# SCH_simple-car_2026-01-17.net
KiCad netlist of a schematic drawn in EasyEDA
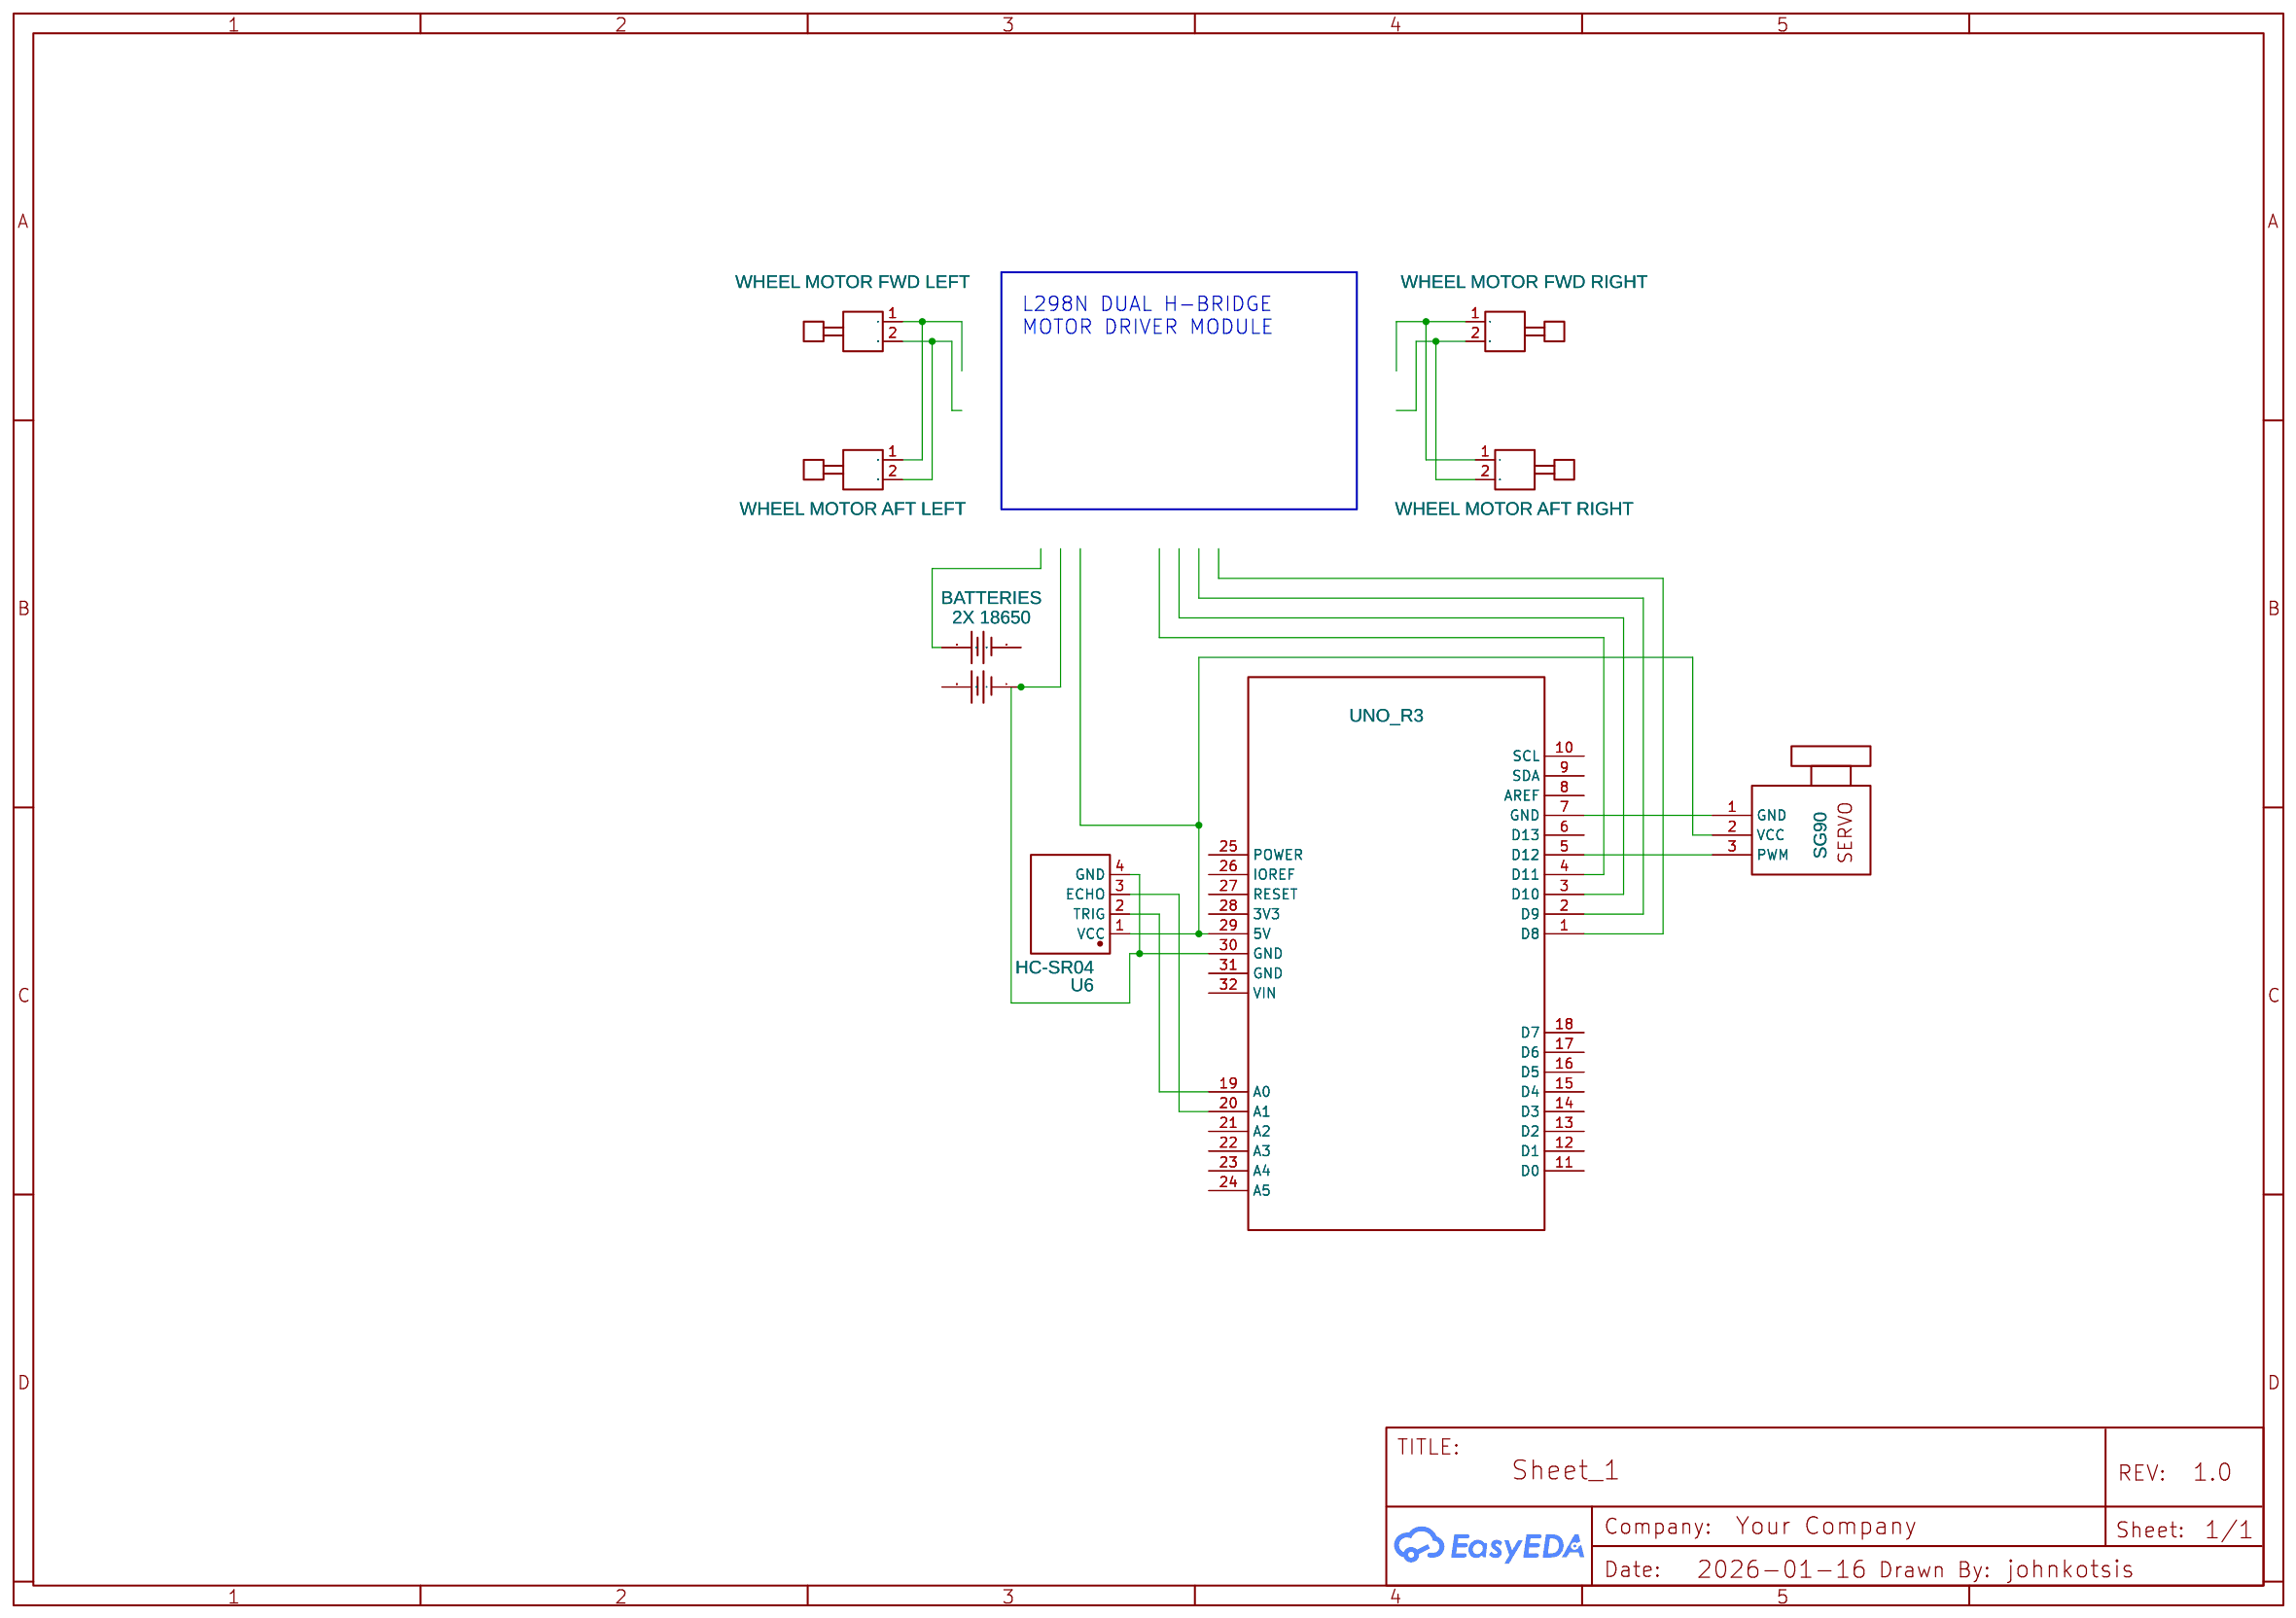
[diagram p0: schematic sheet]

(export (version "E")
  (design (tool "Eeschema 10.0.6"))
  (components
    (comp (ref "BATTERIES")
      (value "2X 18650")
      (fields
        (field (name "Manufacturer Part") "BH-18650-A1BJ034")
        (field (name "Manufacturer") "MYOUNG(美阳)")
      )
      (libsource (lib "") (part "BH-18650-A1BJ034"))
    )
    (comp (ref "P1") (value "UNO_R3") (libsource (lib "") (part "UNO_R3")))
    (comp (ref "U1")
      (value "SG90")
      (fields (field (name "Manufacturer Part") "ServoMotor"))
      (libsource (lib "") (part "SERVO MG995 COPY"))
    )
    (comp (ref "U2")
      (value "WHEEL MOTOR FWD LEFT")
      (fields (field (name "Manufacturer Part") "LCM04084521-B1") (field (name "Manufacturer") "LEADER(立得)"))
      (libsource (lib "") (part "LCM04084521-B1"))
    )
    (comp (ref "U3")
      (value "WHEEL MOTOR FWD RIGHT")
      (fields (field (name "Manufacturer Part") "LCM04084521-B1") (field (name "Manufacturer") "LEADER(立得)"))
      (libsource (lib "") (part "LCM04084521-B1_1"))
    )
    (comp (ref "U4")
      (value "WHEEL MOTOR AFT LEFT")
      (fields (field (name "Manufacturer Part") "LCM04084521-B1") (field (name "Manufacturer") "LEADER(立得)"))
      (libsource (lib "") (part "LCM04084521-B1"))
    )
    (comp (ref "U5")
      (value "WHEEL MOTOR AFT RIGHT")
      (fields (field (name "Manufacturer Part") "LCM04084521-B1") (field (name "Manufacturer") "LEADER(立得)"))
      (libsource (lib "") (part "LCM04084521-B1_1"))
    )
    (comp (ref "U6")
      (value "HC-SR04")
      (fields (field (name "Manufacturer") "Universal Microelectronics"))
      (libsource (lib "") (part "HC-SR04"))
    )
  )
  (nets
    (net (code "1") (name "Net-(P1-5V)") (class "Default")
      (node (ref "P1") (pin "29") (pinfunction "5V_29") (pintype "unspecified"))
      (node (ref "U1") (pin "2") (pinfunction "VCC_2") (pintype "unspecified"))
      (node (ref "U6") (pin "1") (pinfunction "VCC_1") (pintype "unspecified"))
    )
    (net (code "2") (name "Net-(P1-A0)") (class "Default")
      (node (ref "P1") (pin "19") (pinfunction "A0_19") (pintype "unspecified"))
      (node (ref "U6") (pin "2") (pinfunction "TRIG_2") (pintype "unspecified"))
    )
    (net (code "3") (name "Net-(P1-A1)") (class "Default")
      (node (ref "P1") (pin "20") (pinfunction "A1_20") (pintype "unspecified"))
      (node (ref "U6") (pin "3") (pinfunction "ECHO_3") (pintype "unspecified"))
    )
    (net (code "4") (name "Net-(P1-D12)") (class "Default")
      (node (ref "P1") (pin "5") (pinfunction "D12_5") (pintype "unspecified"))
      (node (ref "U1") (pin "3") (pinfunction "PWM_3") (pintype "unspecified"))
    )
    (net (code "5") (name "Net-(U1-GND)") (class "Default")
      (node (ref "P1") (pin "7") (pinfunction "GND_7") (pintype "unspecified"))
      (node (ref "U1") (pin "1") (pinfunction "GND_1") (pintype "unspecified"))
    )
    (net (code "6") (name "Net-(U2-Pad1)") (class "Default")
      (node (ref "U2") (pin "1") (pinfunction "1_1") (pintype "unspecified"))
      (node (ref "U4") (pin "1") (pinfunction "1_1") (pintype "unspecified"))
    )
    (net (code "7") (name "Net-(U2-Pad2)") (class "Default")
      (node (ref "U2") (pin "2") (pinfunction "2_2") (pintype "unspecified"))
      (node (ref "U4") (pin "2") (pinfunction "2_2") (pintype "unspecified"))
    )
    (net (code "8") (name "Net-(U3-Pad1)") (class "Default")
      (node (ref "U3") (pin "1") (pinfunction "1_1") (pintype "unspecified"))
      (node (ref "U5") (pin "1") (pinfunction "1_1") (pintype "unspecified"))
    )
    (net (code "9") (name "Net-(U3-Pad2)") (class "Default")
      (node (ref "U3") (pin "2") (pinfunction "2_2") (pintype "unspecified"))
      (node (ref "U5") (pin "2") (pinfunction "2_2") (pintype "unspecified"))
    )
    (net (code "10") (name "Net-(U6-GND)") (class "Default")
      (node (ref "BATTERIES") (pin "4") (pinfunction "4_4") (pintype "input"))
      (node (ref "P1") (pin "30") (pinfunction "GND_30") (pintype "unspecified"))
      (node (ref "U6") (pin "4") (pinfunction "GND_4") (pintype "unspecified"))
    )
    (net (code "11") (name "unconnected-(BATTERIES-Pad1)") (class "Default")
      (node (ref "BATTERIES") (pin "1") (pinfunction "1_1") (pintype "input"))
    )
    (net (code "12") (name "unconnected-(BATTERIES-Pad2)") (class "Default")
      (node (ref "BATTERIES") (pin "2") (pinfunction "2_2") (pintype "input"))
    )
    (net (code "13") (name "unconnected-(BATTERIES-Pad3)") (class "Default")
      (node (ref "BATTERIES") (pin "3") (pinfunction "3_3") (pintype "input"))
    )
    (net (code "14") (name "unconnected-(P1-3V3-Pad28)") (class "Default")
      (node (ref "P1") (pin "28") (pinfunction "3V3_28") (pintype "unspecified"))
    )
    (net (code "15") (name "unconnected-(P1-A2-Pad21)") (class "Default")
      (node (ref "P1") (pin "21") (pinfunction "A2_21") (pintype "unspecified"))
    )
    (net (code "16") (name "unconnected-(P1-A3-Pad22)") (class "Default")
      (node (ref "P1") (pin "22") (pinfunction "A3_22") (pintype "unspecified"))
    )
    (net (code "17") (name "unconnected-(P1-A4-Pad23)") (class "Default")
      (node (ref "P1") (pin "23") (pinfunction "A4_23") (pintype "unspecified"))
    )
    (net (code "18") (name "unconnected-(P1-A5-Pad24)") (class "Default")
      (node (ref "P1") (pin "24") (pinfunction "A5_24") (pintype "unspecified"))
    )
    (net (code "19") (name "unconnected-(P1-AREF-Pad8)") (class "Default")
      (node (ref "P1") (pin "8") (pinfunction "AREF_8") (pintype "unspecified"))
    )
    (net (code "20") (name "unconnected-(P1-D0-Pad11)") (class "Default")
      (node (ref "P1") (pin "11") (pinfunction "D0_11") (pintype "unspecified"))
    )
    (net (code "21") (name "unconnected-(P1-D1-Pad12)") (class "Default")
      (node (ref "P1") (pin "12") (pinfunction "D1_12") (pintype "unspecified"))
    )
    (net (code "22") (name "unconnected-(P1-D2-Pad13)") (class "Default")
      (node (ref "P1") (pin "13") (pinfunction "D2_13") (pintype "unspecified"))
    )
    (net (code "23") (name "unconnected-(P1-D3-Pad14)") (class "Default")
      (node (ref "P1") (pin "14") (pinfunction "D3_14") (pintype "unspecified"))
    )
    (net (code "24") (name "unconnected-(P1-D4-Pad15)") (class "Default")
      (node (ref "P1") (pin "15") (pinfunction "D4_15") (pintype "unspecified"))
    )
    (net (code "25") (name "unconnected-(P1-D5-Pad16)") (class "Default")
      (node (ref "P1") (pin "16") (pinfunction "D5_16") (pintype "unspecified"))
    )
    (net (code "26") (name "unconnected-(P1-D6-Pad17)") (class "Default")
      (node (ref "P1") (pin "17") (pinfunction "D6_17") (pintype "unspecified"))
    )
    (net (code "27") (name "unconnected-(P1-D7-Pad18)") (class "Default")
      (node (ref "P1") (pin "18") (pinfunction "D7_18") (pintype "unspecified"))
    )
    (net (code "28") (name "unconnected-(P1-D8-Pad1)") (class "Default")
      (node (ref "P1") (pin "1") (pinfunction "D8_1") (pintype "unspecified"))
    )
    (net (code "29") (name "unconnected-(P1-D9-Pad2)") (class "Default")
      (node (ref "P1") (pin "2") (pinfunction "D9_2") (pintype "unspecified"))
    )
    (net (code "30") (name "unconnected-(P1-D10-Pad3)") (class "Default")
      (node (ref "P1") (pin "3") (pinfunction "D10_3") (pintype "unspecified"))
    )
    (net (code "31") (name "unconnected-(P1-D11-Pad4)") (class "Default")
      (node (ref "P1") (pin "4") (pinfunction "D11_4") (pintype "unspecified"))
    )
    (net (code "32") (name "unconnected-(P1-D13-Pad6)") (class "Default")
      (node (ref "P1") (pin "6") (pinfunction "D13_6") (pintype "unspecified"))
    )
    (net (code "33") (name "unconnected-(P1-GND-Pad31)") (class "Default")
      (node (ref "P1") (pin "31") (pinfunction "GND_31") (pintype "unspecified"))
    )
    (net (code "34") (name "unconnected-(P1-IOREF-Pad26)") (class "Default")
      (node (ref "P1") (pin "26") (pinfunction "IOREF_26") (pintype "unspecified"))
    )
    (net (code "35") (name "unconnected-(P1-POWER-Pad25)") (class "Default")
      (node (ref "P1") (pin "25") (pinfunction "POWER_25") (pintype "unspecified"))
    )
    (net (code "36") (name "unconnected-(P1-RESET-Pad27)") (class "Default")
      (node (ref "P1") (pin "27") (pinfunction "RESET_27") (pintype "unspecified"))
    )
    (net (code "37") (name "unconnected-(P1-SCL-Pad10)") (class "Default")
      (node (ref "P1") (pin "10") (pinfunction "SCL_10") (pintype "unspecified"))
    )
    (net (code "38") (name "unconnected-(P1-SDA-Pad9)") (class "Default")
      (node (ref "P1") (pin "9") (pinfunction "SDA_9") (pintype "unspecified"))
    )
    (net (code "39") (name "unconnected-(P1-VIN-Pad32)") (class "Default")
      (node (ref "P1") (pin "32") (pinfunction "VIN_32") (pintype "unspecified"))
    )
  )
)
